# LEDPlate.net
KiCad netlist of a schematic drawn in EAGLE
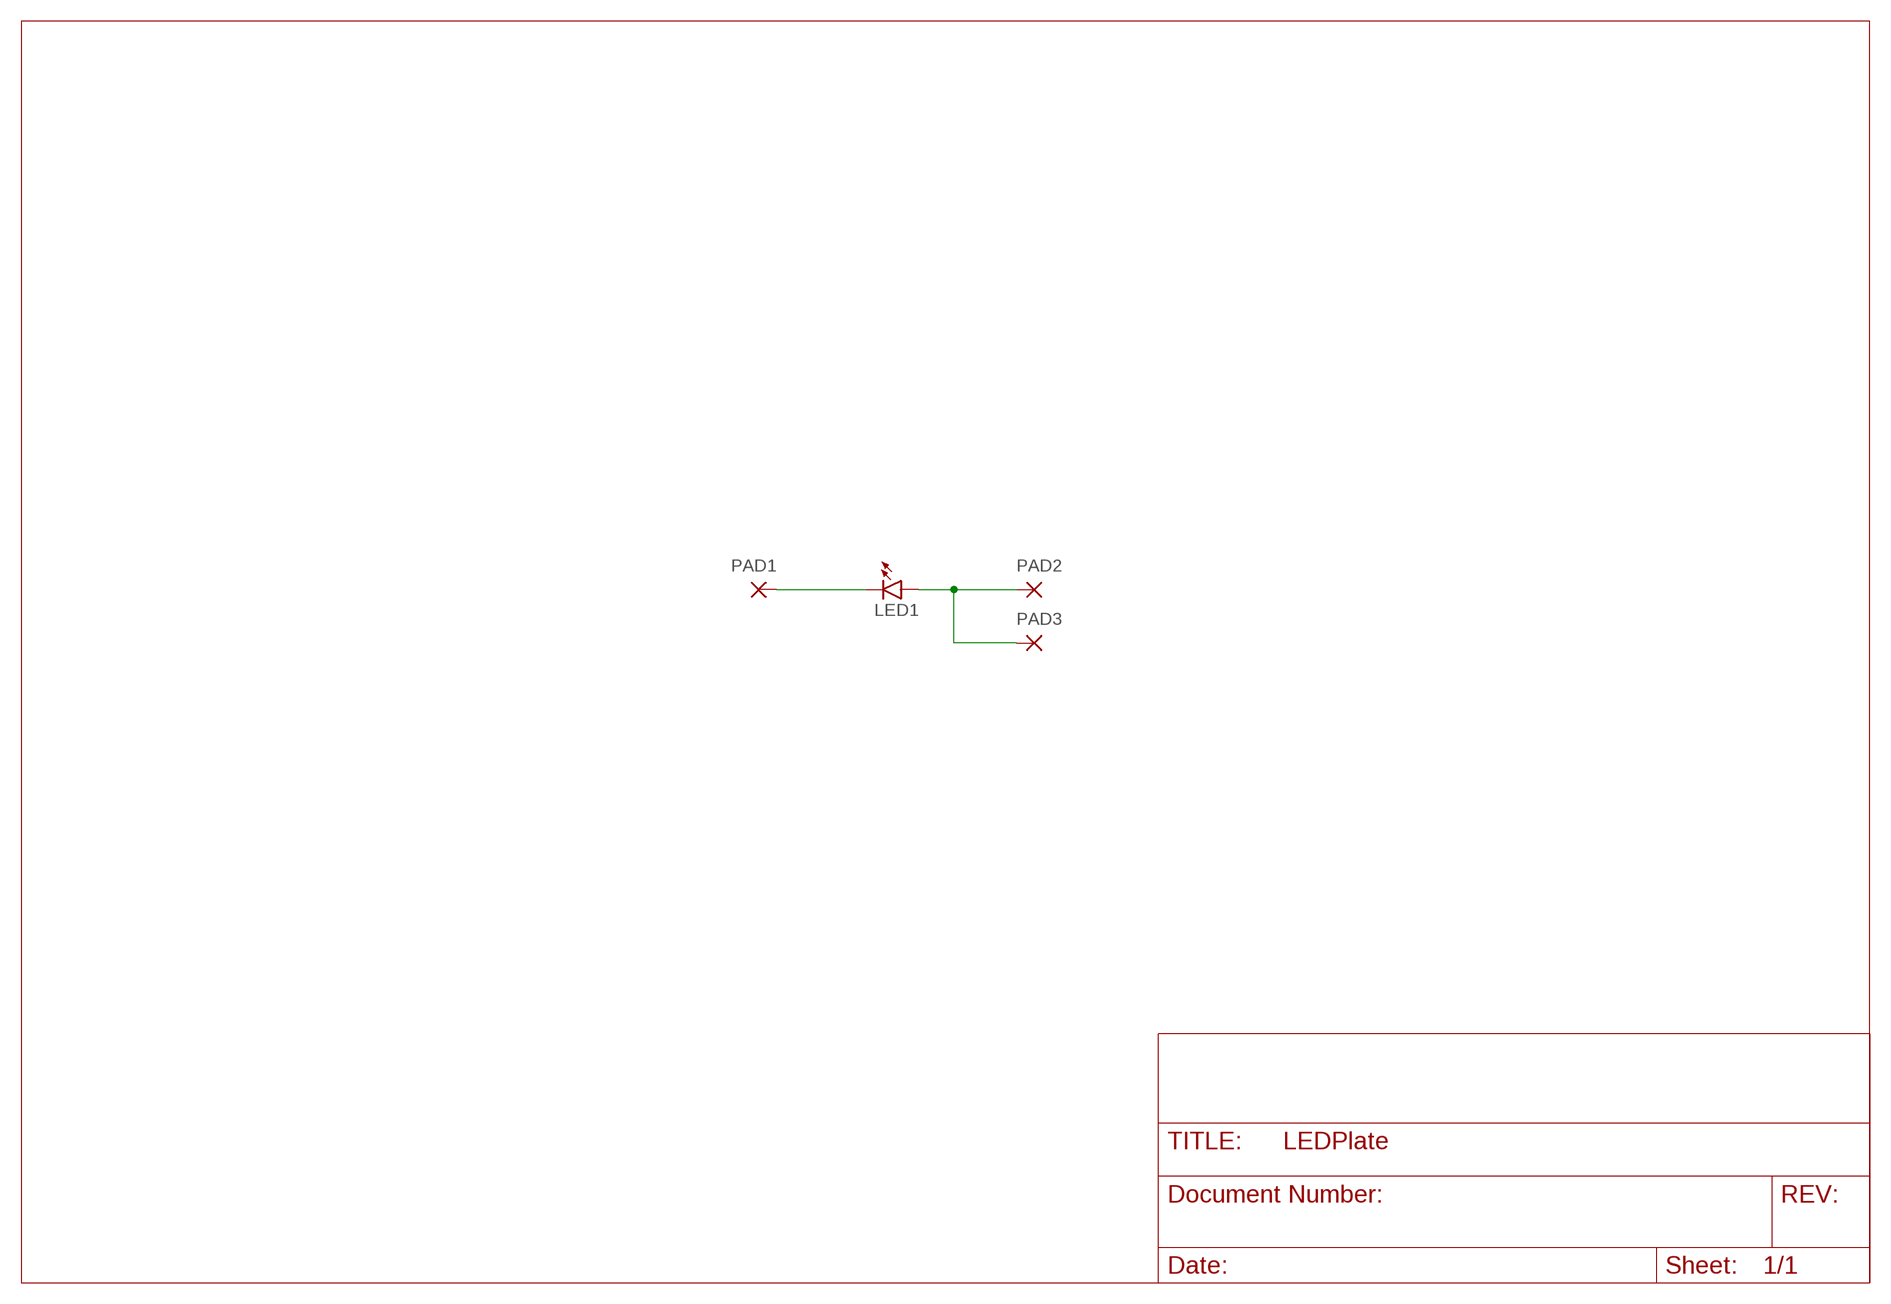
[diagram p0: schematic, sheet 1]

(export (version "E")
  (design (tool "Eeschema 10.0.6"))
  (components
    (comp (ref "LED1")
      (value "LED2")
      (footprint "eagle-import:P-C8WT803")
      (libsource (lib "eagle-import") (part "LED2"))
    )
    (comp (ref "PAD1")
      (value "PAD")
      (footprint "eagle-import:P-SMD1.27X2.54")
      (libsource (lib "eagle-import") (part "PAD"))
    )
    (comp (ref "PAD2")
      (value "PAD")
      (footprint "eagle-import:P-SMD1.27X2.54")
      (libsource (lib "eagle-import") (part "PAD"))
    )
    (comp (ref "PAD3")
      (value "PAD")
      (footprint "eagle-import:P-SMD1.27X2.54")
      (libsource (lib "eagle-import") (part "PAD"))
    )
  )
  (nets
    (net (code "1") (name "Net-(PAD1-P)") (class "Default")
      (node (ref "LED1") (pin "C") (pinfunction "C_C") (pintype "passive"))
      (node (ref "PAD1") (pin "1") (pinfunction "P_1") (pintype "passive"))
    )
    (net (code "2") (name "Net-(PAD2-P)") (class "Default")
      (node (ref "LED1") (pin "A") (pinfunction "A_A") (pintype "passive"))
      (node (ref "PAD2") (pin "1") (pinfunction "P_1") (pintype "passive"))
      (node (ref "PAD3") (pin "1") (pinfunction "P_1") (pintype "passive"))
    )
  )
)
